# AS5048A_ext.net
KiCad netlist of a schematic drawn in EAGLE
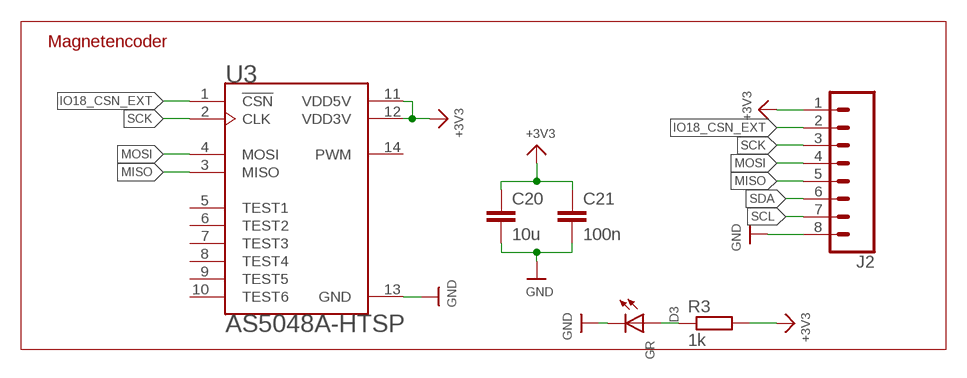
[diagram p0: schematic, sheet 1]

(export (version "E")
  (design (tool "Eeschema 10.0.6"))
  (components
    (comp (ref "C20")
      (value "10u")
      (footprint "eagle-import:C0805")
      (libsource (lib "eagle-import") (part "C-EUC0805"))
    )
    (comp (ref "C21")
      (value "100n")
      (footprint "eagle-import:C0805")
      (libsource (lib "eagle-import") (part "C-EUC0805"))
    )
    (comp (ref "D3")
      (value "GR")
      (footprint "eagle-import:CHIP-LED0805")
      (libsource (lib "eagle-import") (part "LEDCHIP-LED0805"))
    )
    (comp (ref "J2")
      (value "CONN_08BM08B-SRSS-TB")
      (footprint "eagle-import:BM08B-SRSS-TB")
      (libsource (lib "eagle-import") (part "CONN_08BM08B-SRSS-TB"))
    )
    (comp (ref "R3")
      (value "1k")
      (footprint "eagle-import:R0805")
      (libsource (lib "eagle-import") (part "R-EU_R0805"))
    )
    (comp (ref "U3")
      (value "AS5048A-HTSP")
      (footprint "eagle-import:SOP65P640X120-14N")
      (fields (field (name "MF") "ams"))
      (libsource (lib "eagle-import") (part "AS5048A-HTSP"))
    )
  )
  (nets
    (net (code "1") (name "+3V3") (class "Default")
      (node (ref "C20") (pin "1") (pinfunction "1_1") (pintype "passive"))
      (node (ref "C21") (pin "1") (pinfunction "1_1") (pintype "passive"))
      (node (ref "J2") (pin "1") (pinfunction "1_1") (pintype "passive"))
      (node (ref "R3") (pin "2") (pinfunction "2_2") (pintype "passive"))
      (node (ref "U3") (pin "11") (pinfunction "VDD5V_11") (pintype "power_in"))
      (node (ref "U3") (pin "12") (pinfunction "VDD3V_12") (pintype "power_in"))
    )
    (net (code "2") (name "GND") (class "Default")
      (node (ref "C20") (pin "2") (pinfunction "2_2") (pintype "passive"))
      (node (ref "C21") (pin "2") (pinfunction "2_2") (pintype "passive"))
      (node (ref "D3") (pin "C") (pinfunction "C_C") (pintype "passive"))
      (node (ref "J2") (pin "8") (pinfunction "8_8") (pintype "passive"))
      (node (ref "U3") (pin "13") (pinfunction "GND_13") (pintype "passive"))
    )
    (net (code "3") (name "IO18_CSN_EXT") (class "Default")
      (node (ref "J2") (pin "2") (pinfunction "2_2") (pintype "passive"))
      (node (ref "U3") (pin "1") (pinfunction "~{CSN}_1") (pintype "input"))
    )
    (net (code "4") (name "MISO") (class "Default")
      (node (ref "J2") (pin "5") (pinfunction "5_5") (pintype "passive"))
      (node (ref "U3") (pin "3") (pinfunction "MISO_3") (pintype "bidirectional"))
    )
    (net (code "5") (name "MOSI") (class "Default")
      (node (ref "J2") (pin "4") (pinfunction "4_4") (pintype "passive"))
      (node (ref "U3") (pin "4") (pinfunction "MOSI_4") (pintype "input"))
    )
    (net (code "6") (name "Net-(D3-PadA)") (class "Default")
      (node (ref "D3") (pin "A") (pinfunction "A_A") (pintype "passive"))
      (node (ref "R3") (pin "1") (pinfunction "1_1") (pintype "passive"))
    )
    (net (code "7") (name "SCK") (class "Default")
      (node (ref "J2") (pin "3") (pinfunction "3_3") (pintype "passive"))
      (node (ref "U3") (pin "2") (pinfunction "CLK_2") (pintype "input"))
    )
    (net (code "8") (name "SCL") (class "Default")
      (node (ref "J2") (pin "7") (pinfunction "7_7") (pintype "passive"))
    )
    (net (code "9") (name "SDA") (class "Default")
      (node (ref "J2") (pin "6") (pinfunction "6_6") (pintype "passive"))
    )
    (net (code "10") (name "unconnected-(U3-PWM-Pad14)") (class "Default")
      (node (ref "U3") (pin "14") (pinfunction "PWM_14") (pintype "output"))
    )
    (net (code "11") (name "unconnected-(U3-TEST1-Pad5)") (class "Default")
      (node (ref "U3") (pin "5") (pinfunction "TEST1_5") (pintype "bidirectional"))
    )
    (net (code "12") (name "unconnected-(U3-TEST2-Pad6)") (class "Default")
      (node (ref "U3") (pin "6") (pinfunction "TEST2_6") (pintype "bidirectional"))
    )
    (net (code "13") (name "unconnected-(U3-TEST3-Pad7)") (class "Default")
      (node (ref "U3") (pin "7") (pinfunction "TEST3_7") (pintype "bidirectional"))
    )
    (net (code "14") (name "unconnected-(U3-TEST4-Pad8)") (class "Default")
      (node (ref "U3") (pin "8") (pinfunction "TEST4_8") (pintype "bidirectional"))
    )
    (net (code "15") (name "unconnected-(U3-TEST5-Pad9)") (class "Default")
      (node (ref "U3") (pin "9") (pinfunction "TEST5_9") (pintype "bidirectional"))
    )
    (net (code "16") (name "unconnected-(U3-TEST6-Pad10)") (class "Default")
      (node (ref "U3") (pin "10") (pinfunction "TEST6_10") (pintype "bidirectional"))
    )
  )
)
